# DEV_001.net
KiCad netlist of a schematic drawn in EAGLE
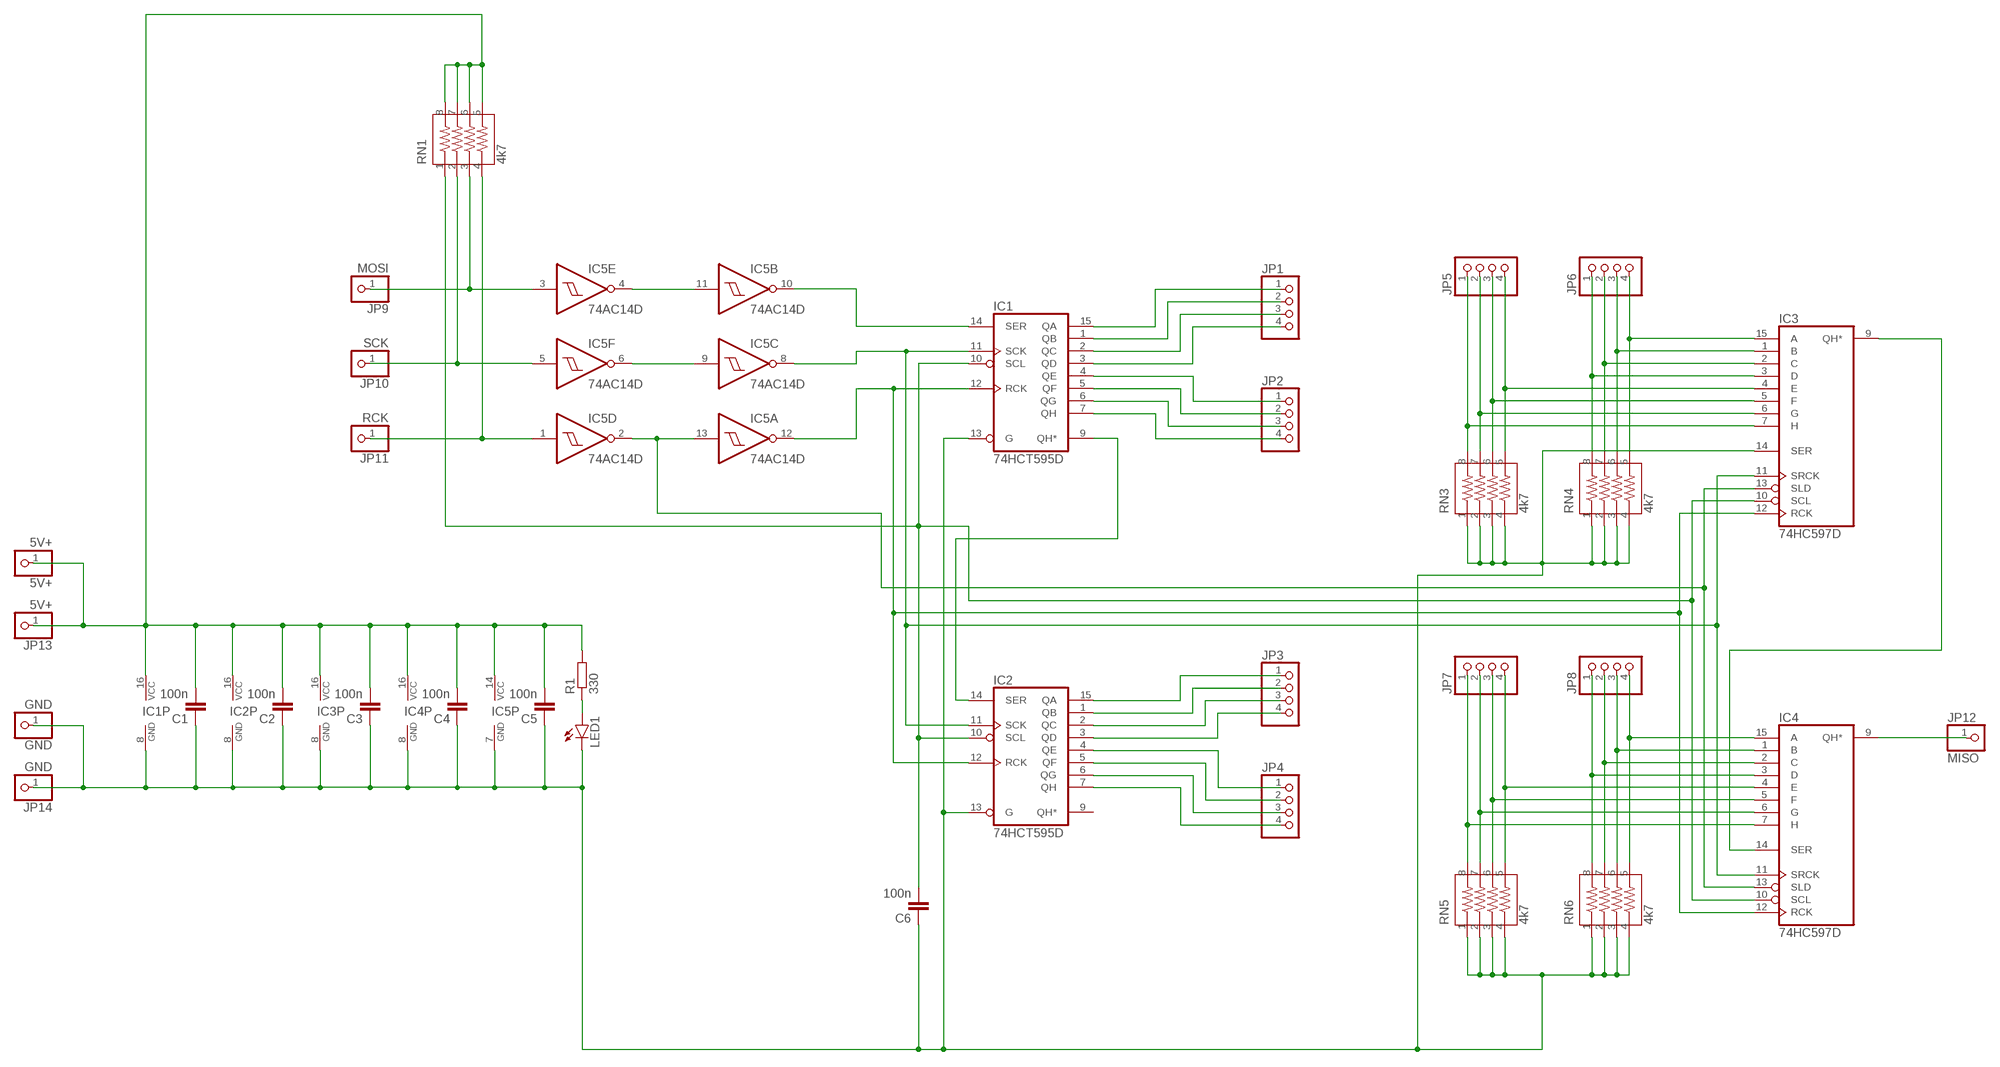
[diagram p0: schematic, sheet 1]

(export (version "E")
  (design (tool "Eeschema 10.0.6"))
  (components
    (comp (ref "5V+")
      (value "5V+")
      (footprint "eagle-import:1X01")
      (libsource (lib "eagle-import") (part "PINHD-1X1"))
    )
    (comp (ref "C1")
      (value "100n")
      (footprint "eagle-import:C1206K")
      (libsource (lib "eagle-import") (part "C-EUC1206K"))
    )
    (comp (ref "C2")
      (value "100n")
      (footprint "eagle-import:C1206K")
      (libsource (lib "eagle-import") (part "C-EUC1206K"))
    )
    (comp (ref "C3")
      (value "100n")
      (footprint "eagle-import:C1206K")
      (libsource (lib "eagle-import") (part "C-EUC1206K"))
    )
    (comp (ref "C4")
      (value "100n")
      (footprint "eagle-import:C1206K")
      (libsource (lib "eagle-import") (part "C-EUC1206K"))
    )
    (comp (ref "C5")
      (value "100n")
      (footprint "eagle-import:C1206K")
      (libsource (lib "eagle-import") (part "C-EUC1206K"))
    )
    (comp (ref "C6")
      (value "100n")
      (footprint "eagle-import:C1206K")
      (libsource (lib "eagle-import") (part "C-EUC1206K"))
    )
    (comp (ref "GND")
      (value "GND")
      (footprint "eagle-import:1X01")
      (libsource (lib "eagle-import") (part "PINHD-1X1"))
    )
    (comp (ref "IC1")
      (value "74HCT595D")
      (footprint "eagle-import:SO16")
      (libsource (lib "eagle-import") (part "74595DHCT"))
    )
    (comp (ref "IC2")
      (value "74HCT595D")
      (footprint "eagle-import:SO16")
      (libsource (lib "eagle-import") (part "74595DHCT"))
    )
    (comp (ref "IC3")
      (value "74HC597D")
      (footprint "eagle-import:SO16")
      (libsource (lib "eagle-import") (part "74597DHC"))
    )
    (comp (ref "IC4")
      (value "74HC597D")
      (footprint "eagle-import:SO16")
      (libsource (lib "eagle-import") (part "74597DHC"))
    )
    (comp (ref "IC5")
      (value "74AC14D")
      (footprint "eagle-import:SO14")
      (libsource (lib "eagle-import") (part "7414DAC"))
    )
    (comp (ref "JP1")
      (value "PINHD-1X4")
      (footprint "eagle-import:1X04")
      (libsource (lib "eagle-import") (part "PINHD-1X4"))
    )
    (comp (ref "JP2")
      (value "PINHD-1X4")
      (footprint "eagle-import:1X04")
      (libsource (lib "eagle-import") (part "PINHD-1X4"))
    )
    (comp (ref "JP3")
      (value "PINHD-1X4")
      (footprint "eagle-import:1X04")
      (libsource (lib "eagle-import") (part "PINHD-1X4"))
    )
    (comp (ref "JP4")
      (value "PINHD-1X4")
      (footprint "eagle-import:1X04")
      (libsource (lib "eagle-import") (part "PINHD-1X4"))
    )
    (comp (ref "JP5")
      (value "PINHD-1X4")
      (footprint "eagle-import:1X04")
      (libsource (lib "eagle-import") (part "PINHD-1X4"))
    )
    (comp (ref "JP6")
      (value "PINHD-1X4")
      (footprint "eagle-import:1X04")
      (libsource (lib "eagle-import") (part "PINHD-1X4"))
    )
    (comp (ref "JP7")
      (value "PINHD-1X4")
      (footprint "eagle-import:1X04")
      (libsource (lib "eagle-import") (part "PINHD-1X4"))
    )
    (comp (ref "JP8")
      (value "PINHD-1X4")
      (footprint "eagle-import:1X04")
      (libsource (lib "eagle-import") (part "PINHD-1X4"))
    )
    (comp (ref "JP9")
      (value "MOSI")
      (footprint "eagle-import:1X01")
      (libsource (lib "eagle-import") (part "PINHD-1X1"))
    )
    (comp (ref "JP10")
      (value "SCK")
      (footprint "eagle-import:1X01")
      (libsource (lib "eagle-import") (part "PINHD-1X1"))
    )
    (comp (ref "JP11")
      (value "RCK")
      (footprint "eagle-import:1X01")
      (libsource (lib "eagle-import") (part "PINHD-1X1"))
    )
    (comp (ref "JP12")
      (value "MISO")
      (footprint "eagle-import:1X01")
      (libsource (lib "eagle-import") (part "PINHD-1X1"))
    )
    (comp (ref "JP13")
      (value "5V+")
      (footprint "eagle-import:1X01")
      (libsource (lib "eagle-import") (part "PINHD-1X1"))
    )
    (comp (ref "JP14")
      (value "GND")
      (footprint "eagle-import:1X01")
      (libsource (lib "eagle-import") (part "PINHD-1X1"))
    )
    (comp (ref "LED1")
      (value "LEDCHIPLED_0805")
      (footprint "eagle-import:CHIPLED_0805")
      (libsource (lib "eagle-import") (part "LEDCHIPLED_0805"))
    )
    (comp (ref "R1")
      (value "330")
      (footprint "eagle-import:R1206")
      (libsource (lib "eagle-import") (part "R-EU_R1206"))
    )
    (comp (ref "RN1")
      (value "4k7")
      (footprint "eagle-import:742C083103JP")
      (fields
        (field (name "MANUFACTURER") "CTS Resistor Products")
        (field (name "MPN") "742C083103JP")
        (field (name "CREATED_BY") "PCBLayout.com")
      )
      (libsource (lib "eagle-import") (part "742C083103JP"))
    )
    (comp (ref "RN3")
      (value "4k7")
      (footprint "eagle-import:742C083103JP")
      (fields
        (field (name "MANUFACTURER") "CTS Resistor Products")
        (field (name "MPN") "742C083103JP")
        (field (name "CREATED_BY") "PCBLayout.com")
      )
      (libsource (lib "eagle-import") (part "742C083103JP"))
    )
    (comp (ref "RN4")
      (value "4k7")
      (footprint "eagle-import:742C083103JP")
      (fields
        (field (name "MANUFACTURER") "CTS Resistor Products")
        (field (name "MPN") "742C083103JP")
        (field (name "CREATED_BY") "PCBLayout.com")
      )
      (libsource (lib "eagle-import") (part "742C083103JP"))
    )
    (comp (ref "RN5")
      (value "4k7")
      (footprint "eagle-import:742C083103JP")
      (fields
        (field (name "MANUFACTURER") "CTS Resistor Products")
        (field (name "MPN") "742C083103JP")
        (field (name "CREATED_BY") "PCBLayout.com")
      )
      (libsource (lib "eagle-import") (part "742C083103JP"))
    )
    (comp (ref "RN6")
      (value "4k7")
      (footprint "eagle-import:742C083103JP")
      (fields
        (field (name "MANUFACTURER") "CTS Resistor Products")
        (field (name "MPN") "742C083103JP")
        (field (name "CREATED_BY") "PCBLayout.com")
      )
      (libsource (lib "eagle-import") (part "742C083103JP"))
    )
  )
  (nets
    (net (code "1") (name "Net-(IC1A-G)") (class "Default")
      (node (ref "C1") (pin "1") (pinfunction "1_1") (pintype "passive"))
      (node (ref "C2") (pin "1") (pinfunction "1_1") (pintype "passive"))
      (node (ref "C3") (pin "1") (pinfunction "1_1") (pintype "passive"))
      (node (ref "C4") (pin "1") (pinfunction "1_1") (pintype "passive"))
      (node (ref "C5") (pin "1") (pinfunction "1_1") (pintype "passive"))
      (node (ref "C6") (pin "1") (pinfunction "1_1") (pintype "passive"))
      (node (ref "GND") (pin "1") (pinfunction "1_1") (pintype "passive"))
      (node (ref "IC1") (pin "13") (pinfunction "G_13") (pintype "input"))
      (node (ref "IC1") (pin "8") (pinfunction "GND_8") (pintype "power_in"))
      (node (ref "IC2") (pin "13") (pinfunction "G_13") (pintype "input"))
      (node (ref "IC2") (pin "8") (pinfunction "GND_8") (pintype "power_in"))
      (node (ref "IC3") (pin "14") (pinfunction "SER_14") (pintype "input"))
      (node (ref "IC3") (pin "8") (pinfunction "GND_8") (pintype "power_in"))
      (node (ref "IC4") (pin "8") (pinfunction "GND_8") (pintype "power_in"))
      (node (ref "IC5") (pin "7") (pinfunction "GND_7") (pintype "power_in"))
      (node (ref "JP14") (pin "1") (pinfunction "1_1") (pintype "passive"))
      (node (ref "LED1") (pin "C") (pinfunction "C_C") (pintype "passive"))
      (node (ref "RN3") (pin "1") (pinfunction "1_1") (pintype "passive"))
      (node (ref "RN3") (pin "2") (pinfunction "2_2") (pintype "passive"))
      (node (ref "RN3") (pin "3") (pinfunction "3_3") (pintype "passive"))
      (node (ref "RN3") (pin "4") (pinfunction "4_4") (pintype "passive"))
      (node (ref "RN4") (pin "1") (pinfunction "1_1") (pintype "passive"))
      (node (ref "RN4") (pin "2") (pinfunction "2_2") (pintype "passive"))
      (node (ref "RN4") (pin "3") (pinfunction "3_3") (pintype "passive"))
      (node (ref "RN4") (pin "4") (pinfunction "4_4") (pintype "passive"))
      (node (ref "RN5") (pin "1") (pinfunction "1_1") (pintype "passive"))
      (node (ref "RN5") (pin "2") (pinfunction "2_2") (pintype "passive"))
      (node (ref "RN5") (pin "3") (pinfunction "3_3") (pintype "passive"))
      (node (ref "RN5") (pin "4") (pinfunction "4_4") (pintype "passive"))
      (node (ref "RN6") (pin "1") (pinfunction "1_1") (pintype "passive"))
      (node (ref "RN6") (pin "2") (pinfunction "2_2") (pintype "passive"))
      (node (ref "RN6") (pin "3") (pinfunction "3_3") (pintype "passive"))
      (node (ref "RN6") (pin "4") (pinfunction "4_4") (pintype "passive"))
    )
    (net (code "2") (name "Net-(IC1A-QA)") (class "Default")
      (node (ref "IC1") (pin "15") (pinfunction "QA_15") (pintype "tri_state"))
      (node (ref "JP1") (pin "1") (pinfunction "1_1") (pintype "passive"))
    )
    (net (code "3") (name "Net-(IC1A-QB)") (class "Default")
      (node (ref "IC1") (pin "1") (pinfunction "QB_1") (pintype "tri_state"))
      (node (ref "JP1") (pin "2") (pinfunction "2_2") (pintype "passive"))
    )
    (net (code "4") (name "Net-(IC1A-QC)") (class "Default")
      (node (ref "IC1") (pin "2") (pinfunction "QC_2") (pintype "tri_state"))
      (node (ref "JP1") (pin "3") (pinfunction "3_3") (pintype "passive"))
    )
    (net (code "5") (name "Net-(IC1A-QD)") (class "Default")
      (node (ref "IC1") (pin "3") (pinfunction "QD_3") (pintype "tri_state"))
      (node (ref "JP1") (pin "4") (pinfunction "4_4") (pintype "passive"))
    )
    (net (code "6") (name "Net-(IC1A-QE)") (class "Default")
      (node (ref "IC1") (pin "4") (pinfunction "QE_4") (pintype "tri_state"))
      (node (ref "JP2") (pin "1") (pinfunction "1_1") (pintype "passive"))
    )
    (net (code "7") (name "Net-(IC1A-QF)") (class "Default")
      (node (ref "IC1") (pin "5") (pinfunction "QF_5") (pintype "tri_state"))
      (node (ref "JP2") (pin "2") (pinfunction "2_2") (pintype "passive"))
    )
    (net (code "8") (name "Net-(IC1A-QG)") (class "Default")
      (node (ref "IC1") (pin "6") (pinfunction "QG_6") (pintype "tri_state"))
      (node (ref "JP2") (pin "3") (pinfunction "3_3") (pintype "passive"))
    )
    (net (code "9") (name "Net-(IC1A-QH)") (class "Default")
      (node (ref "IC1") (pin "7") (pinfunction "QH_7") (pintype "tri_state"))
      (node (ref "JP2") (pin "4") (pinfunction "4_4") (pintype "passive"))
    )
    (net (code "10") (name "Net-(IC1A-QH*)") (class "Default")
      (node (ref "IC1") (pin "9") (pinfunction "QH*_9") (pintype "tri_state"))
      (node (ref "IC2") (pin "14") (pinfunction "SER_14") (pintype "input"))
    )
    (net (code "11") (name "Net-(IC1A-RCK)") (class "Default")
      (node (ref "IC1") (pin "12") (pinfunction "RCK_12") (pintype "input"))
      (node (ref "IC2") (pin "12") (pinfunction "RCK_12") (pintype "input"))
      (node (ref "IC3") (pin "12") (pinfunction "RCK_12") (pintype "input"))
      (node (ref "IC4") (pin "12") (pinfunction "RCK_12") (pintype "input"))
      (node (ref "IC5") (pin "12") (pinfunction "O_12") (pintype "output"))
    )
    (net (code "12") (name "Net-(IC1A-SCK)") (class "Default")
      (node (ref "IC1") (pin "11") (pinfunction "SCK_11") (pintype "input"))
      (node (ref "IC2") (pin "11") (pinfunction "SCK_11") (pintype "input"))
      (node (ref "IC3") (pin "11") (pinfunction "SRCK_11") (pintype "input"))
      (node (ref "IC4") (pin "11") (pinfunction "SRCK_11") (pintype "input"))
      (node (ref "IC5") (pin "8") (pinfunction "O_8") (pintype "output"))
    )
    (net (code "13") (name "Net-(IC1A-SCL)") (class "Default")
      (node (ref "C6") (pin "2") (pinfunction "2_2") (pintype "passive"))
      (node (ref "IC1") (pin "10") (pinfunction "SCL_10") (pintype "input"))
      (node (ref "IC2") (pin "10") (pinfunction "SCL_10") (pintype "input"))
      (node (ref "IC3") (pin "10") (pinfunction "SCL_10") (pintype "input"))
      (node (ref "IC4") (pin "10") (pinfunction "SCL_10") (pintype "input"))
      (node (ref "RN1") (pin "1") (pinfunction "1_1") (pintype "passive"))
    )
    (net (code "14") (name "Net-(IC1A-SER)") (class "Default")
      (node (ref "IC1") (pin "14") (pinfunction "SER_14") (pintype "input"))
      (node (ref "IC5") (pin "10") (pinfunction "O_10") (pintype "output"))
    )
    (net (code "15") (name "Net-(IC1B-VCC)") (class "Default")
      (node (ref "5V+") (pin "1") (pinfunction "1_1") (pintype "passive"))
      (node (ref "C1") (pin "2") (pinfunction "2_2") (pintype "passive"))
      (node (ref "C2") (pin "2") (pinfunction "2_2") (pintype "passive"))
      (node (ref "C3") (pin "2") (pinfunction "2_2") (pintype "passive"))
      (node (ref "C4") (pin "2") (pinfunction "2_2") (pintype "passive"))
      (node (ref "C5") (pin "2") (pinfunction "2_2") (pintype "passive"))
      (node (ref "IC1") (pin "16") (pinfunction "VCC_16") (pintype "power_in"))
      (node (ref "IC2") (pin "16") (pinfunction "VCC_16") (pintype "power_in"))
      (node (ref "IC3") (pin "16") (pinfunction "VCC_16") (pintype "power_in"))
      (node (ref "IC4") (pin "16") (pinfunction "VCC_16") (pintype "power_in"))
      (node (ref "IC5") (pin "14") (pinfunction "VCC_14") (pintype "power_in"))
      (node (ref "JP13") (pin "1") (pinfunction "1_1") (pintype "passive"))
      (node (ref "R1") (pin "2") (pinfunction "2_2") (pintype "passive"))
      (node (ref "RN1") (pin "5") (pinfunction "5_5") (pintype "passive"))
      (node (ref "RN1") (pin "6") (pinfunction "6_6") (pintype "passive"))
      (node (ref "RN1") (pin "7") (pinfunction "7_7") (pintype "passive"))
      (node (ref "RN1") (pin "8") (pinfunction "8_8") (pintype "passive"))
    )
    (net (code "16") (name "Net-(IC2A-QA)") (class "Default")
      (node (ref "IC2") (pin "15") (pinfunction "QA_15") (pintype "tri_state"))
      (node (ref "JP3") (pin "1") (pinfunction "1_1") (pintype "passive"))
    )
    (net (code "17") (name "Net-(IC2A-QB)") (class "Default")
      (node (ref "IC2") (pin "1") (pinfunction "QB_1") (pintype "tri_state"))
      (node (ref "JP3") (pin "2") (pinfunction "2_2") (pintype "passive"))
    )
    (net (code "18") (name "Net-(IC2A-QC)") (class "Default")
      (node (ref "IC2") (pin "2") (pinfunction "QC_2") (pintype "tri_state"))
      (node (ref "JP3") (pin "3") (pinfunction "3_3") (pintype "passive"))
    )
    (net (code "19") (name "Net-(IC2A-QD)") (class "Default")
      (node (ref "IC2") (pin "3") (pinfunction "QD_3") (pintype "tri_state"))
      (node (ref "JP3") (pin "4") (pinfunction "4_4") (pintype "passive"))
    )
    (net (code "20") (name "Net-(IC2A-QE)") (class "Default")
      (node (ref "IC2") (pin "4") (pinfunction "QE_4") (pintype "tri_state"))
      (node (ref "JP4") (pin "1") (pinfunction "1_1") (pintype "passive"))
    )
    (net (code "21") (name "Net-(IC2A-QF)") (class "Default")
      (node (ref "IC2") (pin "5") (pinfunction "QF_5") (pintype "tri_state"))
      (node (ref "JP4") (pin "2") (pinfunction "2_2") (pintype "passive"))
    )
    (net (code "22") (name "Net-(IC2A-QG)") (class "Default")
      (node (ref "IC2") (pin "6") (pinfunction "QG_6") (pintype "tri_state"))
      (node (ref "JP4") (pin "3") (pinfunction "3_3") (pintype "passive"))
    )
    (net (code "23") (name "Net-(IC2A-QH)") (class "Default")
      (node (ref "IC2") (pin "7") (pinfunction "QH_7") (pintype "tri_state"))
      (node (ref "JP4") (pin "4") (pinfunction "4_4") (pintype "passive"))
    )
    (net (code "24") (name "Net-(IC3A-A)") (class "Default")
      (node (ref "IC3") (pin "15") (pinfunction "A_15") (pintype "input"))
      (node (ref "JP6") (pin "4") (pinfunction "4_4") (pintype "passive"))
      (node (ref "RN4") (pin "5") (pinfunction "5_5") (pintype "passive"))
    )
    (net (code "25") (name "Net-(IC3A-B)") (class "Default")
      (node (ref "IC3") (pin "1") (pinfunction "B_1") (pintype "input"))
      (node (ref "JP6") (pin "3") (pinfunction "3_3") (pintype "passive"))
      (node (ref "RN4") (pin "6") (pinfunction "6_6") (pintype "passive"))
    )
    (net (code "26") (name "Net-(IC3A-C)") (class "Default")
      (node (ref "IC3") (pin "2") (pinfunction "C_2") (pintype "input"))
      (node (ref "JP6") (pin "2") (pinfunction "2_2") (pintype "passive"))
      (node (ref "RN4") (pin "7") (pinfunction "7_7") (pintype "passive"))
    )
    (net (code "27") (name "Net-(IC3A-D)") (class "Default")
      (node (ref "IC3") (pin "3") (pinfunction "D_3") (pintype "input"))
      (node (ref "JP6") (pin "1") (pinfunction "1_1") (pintype "passive"))
      (node (ref "RN4") (pin "8") (pinfunction "8_8") (pintype "passive"))
    )
    (net (code "28") (name "Net-(IC3A-E)") (class "Default")
      (node (ref "IC3") (pin "4") (pinfunction "E_4") (pintype "input"))
      (node (ref "JP5") (pin "4") (pinfunction "4_4") (pintype "passive"))
      (node (ref "RN3") (pin "5") (pinfunction "5_5") (pintype "passive"))
    )
    (net (code "29") (name "Net-(IC3A-F)") (class "Default")
      (node (ref "IC3") (pin "5") (pinfunction "F_5") (pintype "input"))
      (node (ref "JP5") (pin "3") (pinfunction "3_3") (pintype "passive"))
      (node (ref "RN3") (pin "6") (pinfunction "6_6") (pintype "passive"))
    )
    (net (code "30") (name "Net-(IC3A-G)") (class "Default")
      (node (ref "IC3") (pin "6") (pinfunction "G_6") (pintype "input"))
      (node (ref "JP5") (pin "2") (pinfunction "2_2") (pintype "passive"))
      (node (ref "RN3") (pin "7") (pinfunction "7_7") (pintype "passive"))
    )
    (net (code "31") (name "Net-(IC3A-H)") (class "Default")
      (node (ref "IC3") (pin "7") (pinfunction "H_7") (pintype "input"))
      (node (ref "JP5") (pin "1") (pinfunction "1_1") (pintype "passive"))
      (node (ref "RN3") (pin "8") (pinfunction "8_8") (pintype "passive"))
    )
    (net (code "32") (name "Net-(IC3A-QH*)") (class "Default")
      (node (ref "IC3") (pin "9") (pinfunction "QH*_9") (pintype "output"))
      (node (ref "IC4") (pin "14") (pinfunction "SER_14") (pintype "input"))
    )
    (net (code "33") (name "Net-(IC3A-SLD)") (class "Default")
      (node (ref "IC3") (pin "13") (pinfunction "SLD_13") (pintype "input"))
      (node (ref "IC4") (pin "13") (pinfunction "SLD_13") (pintype "input"))
      (node (ref "IC5") (pin "13") (pinfunction "I_13") (pintype "input"))
      (node (ref "IC5") (pin "2") (pinfunction "O_2") (pintype "output"))
    )
    (net (code "34") (name "Net-(IC4A-A)") (class "Default")
      (node (ref "IC4") (pin "15") (pinfunction "A_15") (pintype "input"))
      (node (ref "JP8") (pin "4") (pinfunction "4_4") (pintype "passive"))
      (node (ref "RN6") (pin "5") (pinfunction "5_5") (pintype "passive"))
    )
    (net (code "35") (name "Net-(IC4A-B)") (class "Default")
      (node (ref "IC4") (pin "1") (pinfunction "B_1") (pintype "input"))
      (node (ref "JP8") (pin "3") (pinfunction "3_3") (pintype "passive"))
      (node (ref "RN6") (pin "6") (pinfunction "6_6") (pintype "passive"))
    )
    (net (code "36") (name "Net-(IC4A-C)") (class "Default")
      (node (ref "IC4") (pin "2") (pinfunction "C_2") (pintype "input"))
      (node (ref "JP8") (pin "2") (pinfunction "2_2") (pintype "passive"))
      (node (ref "RN6") (pin "7") (pinfunction "7_7") (pintype "passive"))
    )
    (net (code "37") (name "Net-(IC4A-D)") (class "Default")
      (node (ref "IC4") (pin "3") (pinfunction "D_3") (pintype "input"))
      (node (ref "JP8") (pin "1") (pinfunction "1_1") (pintype "passive"))
      (node (ref "RN6") (pin "8") (pinfunction "8_8") (pintype "passive"))
    )
    (net (code "38") (name "Net-(IC4A-E)") (class "Default")
      (node (ref "IC4") (pin "4") (pinfunction "E_4") (pintype "input"))
      (node (ref "JP7") (pin "4") (pinfunction "4_4") (pintype "passive"))
      (node (ref "RN5") (pin "5") (pinfunction "5_5") (pintype "passive"))
    )
    (net (code "39") (name "Net-(IC4A-F)") (class "Default")
      (node (ref "IC4") (pin "5") (pinfunction "F_5") (pintype "input"))
      (node (ref "JP7") (pin "3") (pinfunction "3_3") (pintype "passive"))
      (node (ref "RN5") (pin "6") (pinfunction "6_6") (pintype "passive"))
    )
    (net (code "40") (name "Net-(IC4A-G)") (class "Default")
      (node (ref "IC4") (pin "6") (pinfunction "G_6") (pintype "input"))
      (node (ref "JP7") (pin "2") (pinfunction "2_2") (pintype "passive"))
      (node (ref "RN5") (pin "7") (pinfunction "7_7") (pintype "passive"))
    )
    (net (code "41") (name "Net-(IC4A-H)") (class "Default")
      (node (ref "IC4") (pin "7") (pinfunction "H_7") (pintype "input"))
      (node (ref "JP7") (pin "1") (pinfunction "1_1") (pintype "passive"))
      (node (ref "RN5") (pin "8") (pinfunction "8_8") (pintype "passive"))
    )
    (net (code "42") (name "Net-(IC4A-QH*)") (class "Default")
      (node (ref "IC4") (pin "9") (pinfunction "QH*_9") (pintype "output"))
      (node (ref "JP12") (pin "1") (pinfunction "1_1") (pintype "passive"))
    )
    (net (code "43") (name "Net-(IC5B-I)") (class "Default")
      (node (ref "IC5") (pin "11") (pinfunction "I_11") (pintype "input"))
      (node (ref "IC5") (pin "4") (pinfunction "O_4") (pintype "output"))
    )
    (net (code "44") (name "Net-(IC5C-I)") (class "Default")
      (node (ref "IC5") (pin "6") (pinfunction "O_6") (pintype "output"))
      (node (ref "IC5") (pin "9") (pinfunction "I_9") (pintype "input"))
    )
    (net (code "45") (name "Net-(IC5D-I)") (class "Default")
      (node (ref "IC5") (pin "1") (pinfunction "I_1") (pintype "input"))
      (node (ref "JP11") (pin "1") (pinfunction "1_1") (pintype "passive"))
      (node (ref "RN1") (pin "4") (pinfunction "4_4") (pintype "passive"))
    )
    (net (code "46") (name "Net-(IC5E-I)") (class "Default")
      (node (ref "IC5") (pin "3") (pinfunction "I_3") (pintype "input"))
      (node (ref "JP9") (pin "1") (pinfunction "1_1") (pintype "passive"))
      (node (ref "RN1") (pin "3") (pinfunction "3_3") (pintype "passive"))
    )
    (net (code "47") (name "Net-(IC5F-I)") (class "Default")
      (node (ref "IC5") (pin "5") (pinfunction "I_5") (pintype "input"))
      (node (ref "JP10") (pin "1") (pinfunction "1_1") (pintype "passive"))
      (node (ref "RN1") (pin "2") (pinfunction "2_2") (pintype "passive"))
    )
    (net (code "48") (name "Net-(LED1-PadA)") (class "Default")
      (node (ref "LED1") (pin "A") (pinfunction "A_A") (pintype "passive"))
      (node (ref "R1") (pin "1") (pinfunction "1_1") (pintype "passive"))
    )
    (net (code "49") (name "unconnected-(IC2A-QH*-Pad9)") (class "Default")
      (node (ref "IC2") (pin "9") (pinfunction "QH*_9") (pintype "tri_state"))
    )
  )
)
